# Power.net
KiCad netlist of a schematic drawn in Altium Designer
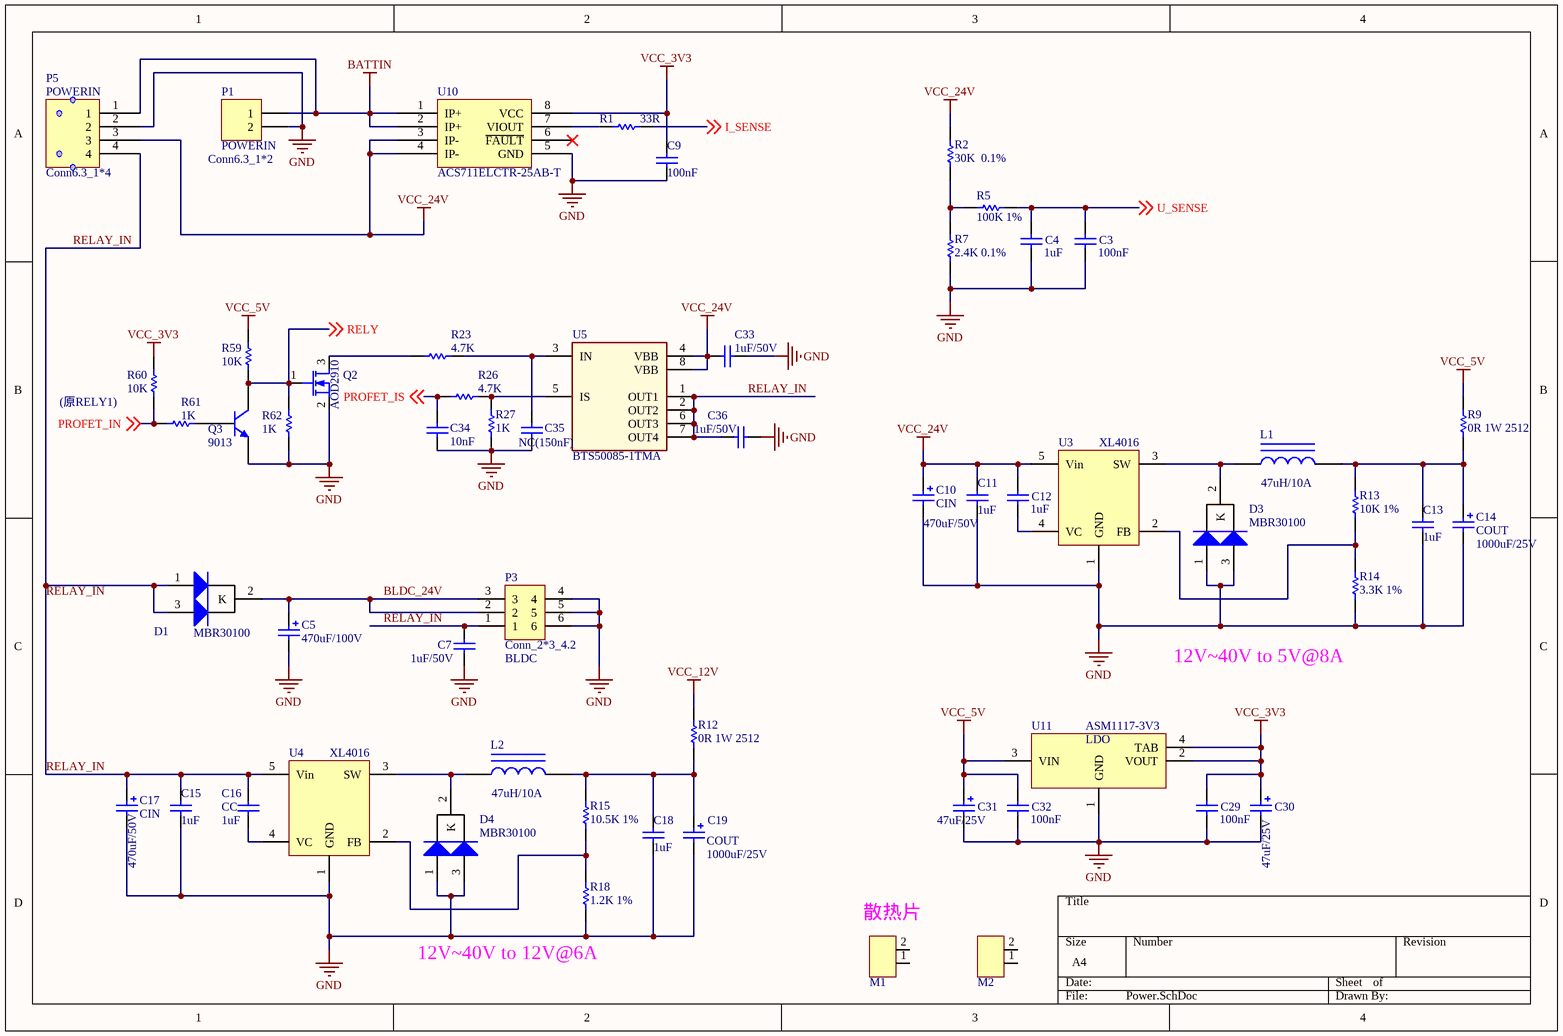
[diagram p0: Power.SchDoc]

(export (version "E")
  (design (tool "Eeschema 10.0.6"))
  (components
    (comp (ref "C3")
      (value "100nF")
      (footprint "C0805")
      (description "Capacitor")
      (fields (field (name "Comment") "Cap") (field (name "PUBLISHER") "Altium Limited"))
      (libsource (lib "boocax_schlib") (part "Cap"))
    )
    (comp (ref "C4")
      (value "1uF")
      (footprint "C0805")
      (description "Capacitor")
      (fields (field (name "Comment") "Cap") (field (name "PUBLISHER") "Altium Limited"))
      (libsource (lib "boocax_schlib") (part "Cap"))
    )
    (comp (ref "C5")
      (value "470uF/100V")
      (footprint "330uF")
      (description "Polarized Capacitor (Radial)")
      (fields (field (name "Comment") "Cap Pol1") (field (name "PUBLISHER") "Altium Limited"))
      (libsource (lib "boocax_schlib") (part "Cap Pol1"))
    )
    (comp (ref "C7")
      (value "1uF/50V")
      (footprint "C0805")
      (description "Capacitor")
      (fields (field (name "Comment") "Cap") (field (name "PUBLISHER") "Altium Limited"))
      (libsource (lib "boocax_schlib") (part "Cap"))
    )
    (comp (ref "C9")
      (value "100nF")
      (footprint "C0805")
      (description "Capacitor")
      (fields (field (name "Comment") "Cap") (field (name "PUBLISHER") "Altium Limited"))
      (libsource (lib "boocax_schlib") (part "Cap"))
    )
    (comp (ref "C10")
      (value "CIN")
      (footprint "CTH-R5-D5")
      (description "Polarized Capacitor (Radial)")
      (fields (field (name "ALTIUM_VALUE") "470uF/50V") (field (name "PUBLISHER") "Altium Limited"))
      (libsource (lib "boocax_schlib") (part "Cap Pol1"))
    )
    (comp (ref "C11")
      (value "1uF")
      (footprint "C0805")
      (description "Capacitor")
      (fields (field (name "Comment") "Cap") (field (name "PUBLISHER") "Altium Limited"))
      (libsource (lib "boocax_schlib") (part "Cap"))
    )
    (comp (ref "C12")
      (value "1uF")
      (footprint "C0805")
      (description "Capacitor")
      (fields (field (name "Comment") "Cap") (field (name "PUBLISHER") "Altium Limited"))
      (libsource (lib "boocax_schlib") (part "Cap"))
    )
    (comp (ref "C13")
      (value "1uF")
      (footprint "C0805")
      (description "Capacitor")
      (fields (field (name "Comment") "Cap") (field (name "PUBLISHER") "Altium Limited"))
      (libsource (lib "boocax_schlib") (part "Cap"))
    )
    (comp (ref "C14")
      (value "COUT")
      (footprint "CTH-R5-D5")
      (description "Polarized Capacitor (Radial)")
      (fields (field (name "ALTIUM_VALUE") "1000uF/25V") (field (name "PUBLISHER") "Altium Limited"))
      (libsource (lib "boocax_schlib") (part "Cap Pol1"))
    )
    (comp (ref "C15")
      (value "1uF")
      (footprint "C0805")
      (description "Capacitor")
      (fields (field (name "Comment") "Cap") (field (name "PUBLISHER") "Altium Limited"))
      (libsource (lib "boocax_schlib") (part "Cap"))
    )
    (comp (ref "C16")
      (value "1uF")
      (footprint "C0805")
      (description "CC")
      (fields (field (name "Comment") "Cap") (field (name "PUBLISHER") "Altium Limited"))
      (libsource (lib "boocax_schlib") (part "Cap"))
    )
    (comp (ref "C17")
      (value "CIN")
      (footprint "CTH-R5-D5")
      (description "Polarized Capacitor (Radial)")
      (fields (field (name "ALTIUM_VALUE") "470uF/50V") (field (name "PUBLISHER") "Altium Limited"))
      (libsource (lib "boocax_schlib") (part "Cap Pol1"))
    )
    (comp (ref "C18")
      (value "1uF")
      (footprint "C0805")
      (description "Capacitor")
      (fields (field (name "Comment") "Cap") (field (name "PUBLISHER") "Altium Limited"))
      (libsource (lib "boocax_schlib") (part "Cap"))
    )
    (comp (ref "C19")
      (value "COUT")
      (footprint "CTH-R5-D5")
      (description "Polarized Capacitor (Radial)")
      (fields (field (name "ALTIUM_VALUE") "1000uF/25V") (field (name "PUBLISHER") "Altium Limited"))
      (libsource (lib "boocax_schlib") (part "Cap Pol1"))
    )
    (comp (ref "C29")
      (value "100nF")
      (footprint "C0805")
      (description "Capacitor")
      (fields (field (name "Comment") "Cap") (field (name "PUBLISHER") "Altium Limited"))
      (libsource (lib "boocax_schlib") (part "Cap"))
    )
    (comp (ref "C30")
      (value "47uF/25V")
      (footprint "CTH-R3-D2.54")
      (description "Polarized Capacitor (Radial)")
      (fields (field (name "Comment") "Cap Pol1") (field (name "PUBLISHER") "Altium Limited"))
      (libsource (lib "boocax_schlib") (part "Cap Pol1"))
    )
    (comp (ref "C31")
      (value "47uF/25V")
      (footprint "CTH-R3-D2.54")
      (description "Polarized Capacitor (Radial)")
      (fields (field (name "Comment") "Cap Pol1") (field (name "PUBLISHER") "Altium Limited"))
      (libsource (lib "boocax_schlib") (part "Cap Pol1"))
    )
    (comp (ref "C32")
      (value "100nF")
      (footprint "C0805")
      (description "Capacitor")
      (fields (field (name "Comment") "Cap") (field (name "PUBLISHER") "Altium Limited"))
      (libsource (lib "boocax_schlib") (part "Cap"))
    )
    (comp (ref "C33")
      (value "1uF/50V")
      (footprint "C0805")
      (description "Capacitor")
      (fields (field (name "Comment") "Cap") (field (name "PUBLISHER") "Altium Limited"))
      (libsource (lib "boocax_schlib") (part "Cap"))
    )
    (comp (ref "C34")
      (value "10nF")
      (footprint "C0805")
      (description "Capacitor")
      (fields (field (name "Comment") "Cap") (field (name "PUBLISHER") "Altium Limited"))
      (libsource (lib "boocax_schlib") (part "Cap"))
    )
    (comp (ref "C35")
      (value "NC(150nF)")
      (footprint "C0805")
      (description "Capacitor")
      (fields (field (name "Comment") "Cap") (field (name "PUBLISHER") "Altium Limited"))
      (libsource (lib "boocax_schlib") (part "Cap"))
    )
    (comp (ref "C36")
      (value "1uF/50V")
      (footprint "C0805")
      (description "Capacitor")
      (fields (field (name "Comment") "Cap") (field (name "PUBLISHER") "Altium Limited"))
      (libsource (lib "boocax_schlib") (part "Cap"))
    )
    (comp (ref "D1")
      (value "MBR30100")
      (footprint "TO-263-3")
      (description "Dual Diode")
      (fields (field (name "PUBLISHER") "Altium Limited"))
      (libsource (lib "boocax_schlib") (part "MBR30100"))
    )
    (comp (ref "D3")
      (value "MBR30100")
      (footprint "BABA03A1:TO-263-3")
      (description "Dual Diode")
      (fields (field (name "PUBLISHER") "Altium Limited"))
      (libsource (lib "boocax_schlib") (part "MBR30100"))
    )
    (comp (ref "D4")
      (value "MBR30100")
      (footprint "BABA03A1:TO-263-3")
      (description "Dual Diode")
      (fields (field (name "PUBLISHER") "Altium Limited"))
      (libsource (lib "boocax_schlib") (part "MBR30100"))
    )
    (comp (ref "L1")
      (value "47uH/10A")
      (footprint "L2210")
      (description "Magnetic-Core Inductor")
      (fields (field (name "Comment") "Inductor Iron") (field (name "PUBLISHER") "Altium Limited"))
      (libsource (lib "boocax_schlib") (part "Inductor Iron"))
    )
    (comp (ref "L2")
      (value "47uH/10A")
      (footprint "L2210")
      (description "Magnetic-Core Inductor")
      (fields (field (name "Comment") "Inductor Iron") (field (name "PUBLISHER") "Altium Limited"))
      (libsource (lib "boocax_schlib") (part "Inductor Iron"))
    )
    (comp (ref "M1")
      (value "SRP")
      (footprint "BABA03A1:SRP-2-15*10")
      (libsource (lib "boocax_schlib") (part "SRP-1"))
    )
    (comp (ref "M2")
      (value "SRP")
      (footprint "BABA03A1:SRP-2-15*10")
      (libsource (lib "boocax_schlib") (part "SRP-1"))
    )
    (comp (ref "P1")
      (value "POWERIN")
      (footprint "DIP2*6.3")
      (description "Conn6.3_1*2")
      (libsource (lib "Miscellaneous Connectors") (part "Header 2"))
    )
    (comp (ref "P3")
      (value "Conn_2*3_4.2")
      (footprint "PIN2X3_4.2")
      (fields (field (name "CONN4.2") "BLDC"))
      (libsource (lib "boocax_schlib") (part "Conn_2*3_4.2"))
    )
    (comp (ref "P5")
      (value "POWERIN")
      (footprint "boocax_schlib:PORT-SIP4-6.3-LOCK")
      (fields (field (name "ALTIUM_UNNAMED_1") "Conn6.3_1*4"))
      (libsource (lib "boocax_schlib") (part "CONN_4PIN"))
    )
    (comp (ref "Q2")
      (value "AOD2910")
      (footprint "boocax_schlib:TO252-D")
      (description "N-Channel MOSFET")
      (fields (field (name "PUBLISHER") "Altium Limited"))
      (libsource (lib "boocax_schlib") (part "MOSFET-N"))
    )
    (comp (ref "Q3")
      (value "9013")
      (footprint "boocax_schlib:BCY-W3/E4")
      (description "NPN General Purpose Amplifier")
      (fields (field (name "PUBLISHER") "Altium Limited"))
      (libsource (lib "Miscellaneous Devices") (part "2N3904"))
    )
    (comp (ref "R1")
      (value "33R")
      (footprint "R0805")
      (description "Resistor")
      (fields (field (name "Comment") "Res1") (field (name "PUBLISHER") "Altium Limited"))
      (libsource (lib "boocax_schlib") (part "Res1"))
    )
    (comp (ref "R2")
      (value "30K  0.1%")
      (footprint "R0805")
      (description "Resistor")
      (fields (field (name "Comment") "Res1") (field (name "PUBLISHER") "Altium Limited"))
      (libsource (lib "boocax_schlib") (part "Res1"))
    )
    (comp (ref "R5")
      (value "100K 1%")
      (footprint "R0805")
      (description "Resistor")
      (fields (field (name "Comment") "Res1") (field (name "PUBLISHER") "Altium Limited"))
      (libsource (lib "boocax_schlib") (part "Res1"))
    )
    (comp (ref "R7")
      (value "2.4K 0.1%")
      (footprint "R0805")
      (description "Resistor")
      (fields (field (name "Comment") "Res1") (field (name "PUBLISHER") "Altium Limited"))
      (libsource (lib "boocax_schlib") (part "Res1"))
    )
    (comp (ref "R9")
      (value "0R 1W 2512")
      (footprint "2512")
      (description "Resistor")
      (fields (field (name "Comment") "Res1") (field (name "PUBLISHER") "Altium Limited"))
      (libsource (lib "boocax_schlib") (part "Res1"))
    )
    (comp (ref "R12")
      (value "0R 1W 2512")
      (footprint "2512")
      (description "Resistor")
      (fields (field (name "Comment") "Res1") (field (name "PUBLISHER") "Altium Limited"))
      (libsource (lib "boocax_schlib") (part "Res1"))
    )
    (comp (ref "R13")
      (value "10K 1%")
      (footprint "R0805")
      (description "Resistor")
      (fields (field (name "Comment") "Res1") (field (name "PUBLISHER") "Altium Limited"))
      (libsource (lib "boocax_schlib") (part "Res1"))
    )
    (comp (ref "R14")
      (value "3.3K 1%")
      (footprint "R0805")
      (description "Resistor")
      (fields (field (name "Comment") "Res1") (field (name "PUBLISHER") "Altium Limited"))
      (libsource (lib "boocax_schlib") (part "Res1"))
    )
    (comp (ref "R15")
      (value "10.5K 1%")
      (footprint "R0805")
      (description "Resistor")
      (fields (field (name "Comment") "Res1") (field (name "PUBLISHER") "Altium Limited"))
      (libsource (lib "boocax_schlib") (part "Res1"))
    )
    (comp (ref "R18")
      (value "1.2K 1%")
      (footprint "R0805")
      (description "Resistor")
      (fields (field (name "Comment") "Res1") (field (name "PUBLISHER") "Altium Limited"))
      (libsource (lib "boocax_schlib") (part "Res1"))
    )
    (comp (ref "R23")
      (value "4.7K")
      (footprint "R0805")
      (description "Resistor")
      (fields (field (name "Comment") "Res1") (field (name "PUBLISHER") "Altium Limited"))
      (libsource (lib "boocax_schlib") (part "Res1"))
    )
    (comp (ref "R26")
      (value "4.7K")
      (footprint "R0805")
      (description "Resistor")
      (fields (field (name "Comment") "Res1") (field (name "PUBLISHER") "Altium Limited"))
      (libsource (lib "boocax_schlib") (part "Res1"))
    )
    (comp (ref "R27")
      (value "1K")
      (footprint "R0805")
      (description "Resistor")
      (fields (field (name "Comment") "Res1") (field (name "PUBLISHER") "Altium Limited"))
      (libsource (lib "boocax_schlib") (part "Res1"))
    )
    (comp (ref "R59")
      (value "10K")
      (footprint "R0805")
      (description "Resistor")
      (fields (field (name "Comment") "Res1") (field (name "PUBLISHER") "Altium Limited"))
      (libsource (lib "boocax_schlib") (part "Res1"))
    )
    (comp (ref "R60")
      (value "10K")
      (footprint "R0805")
      (description "Resistor")
      (fields (field (name "Comment") "Res1") (field (name "PUBLISHER") "Altium Limited"))
      (libsource (lib "boocax_schlib") (part "Res1"))
    )
    (comp (ref "R61")
      (value "1K")
      (footprint "R0805")
      (description "Resistor")
      (fields (field (name "Comment") "Res1") (field (name "PUBLISHER") "Altium Limited"))
      (libsource (lib "boocax_schlib") (part "Res1"))
    )
    (comp (ref "R62")
      (value "1K")
      (footprint "R0805")
      (description "Resistor")
      (fields (field (name "Comment") "Res1") (field (name "PUBLISHER") "Altium Limited"))
      (libsource (lib "boocax_schlib") (part "Res1"))
    )
    (comp (ref "U3")
      (value "XL4016")
      (footprint "TO220-5")
      (description "BUCK DCDC")
      (fields (field (name "PUBLISHER") "Altium Limited"))
      (libsource (lib "boocax_schlib") (part "XL4016"))
    )
    (comp (ref "U4")
      (value "XL4016")
      (footprint "TO220-5")
      (description "BUCK DCDC")
      (fields (field (name "PUBLISHER") "Altium Limited"))
      (libsource (lib "boocax_schlib") (part "XL4016"))
    )
    (comp (ref "U5")
      (value "BTS50085-1TMA")
      (footprint "boocax_schlib:TO127P1385X450-8N-V")
      (description "Smart Highside High Current Power Switch, VBB 70V")
      (fields (field (name "MANUFACTURER") "Infineon Technologies"))
      (libsource (lib "boocax_schlib") (part "BTS50085-1TMA"))
    )
    (comp (ref "U10")
      (value "ACS711ELCTR-25AB-T")
      (footprint "ACS712-SOIC8")
      (libsource (lib "BABA03A-V1") (part "ACS711"))
    )
    (comp (ref "U11")
      (value "ASM1117-3V3")
      (footprint "boocax_schlib:ASM1117-3V3")
      (libsource (lib "boocax_schlib") (part "LDO"))
    )
  )
  (nets
    (net (code "1") (name "/BLDC_24V") (class "Default")
      (node (ref "C5") (pin "1") (pinfunction "1_1") (pintype "passive"))
      (node (ref "D1") (pin "2") (pinfunction "K_2") (pintype "passive"))
      (node (ref "P3") (pin "2") (pinfunction "2_2") (pintype "passive"))
      (node (ref "P3") (pin "3") (pinfunction "3_3") (pintype "passive"))
    )
    (net (code "2") (name "/RELAY_IN") (class "Default")
      (node (ref "C15") (pin "2") (pinfunction "2_2") (pintype "passive"))
      (node (ref "C16") (pin "2") (pinfunction "2_2") (pintype "passive"))
      (node (ref "C17") (pin "1") (pinfunction "1_1") (pintype "passive"))
      (node (ref "C36") (pin "2") (pinfunction "2_2") (pintype "passive"))
      (node (ref "C7") (pin "1") (pinfunction "1_1") (pintype "passive"))
      (node (ref "D1") (pin "1") (pinfunction "A_1") (pintype "passive"))
      (node (ref "D1") (pin "3") (pinfunction "A_3") (pintype "passive"))
      (node (ref "P3") (pin "1") (pinfunction "1_1") (pintype "passive"))
      (node (ref "P5") (pin "4") (pinfunction "4_4") (pintype "passive"))
      (node (ref "U4") (pin "5") (pinfunction "Vin_5") (pintype "passive"))
      (node (ref "U5") (pin "1") (pinfunction "OUT1_1") (pintype "passive"))
      (node (ref "U5") (pin "2") (pinfunction "OUT2_2") (pintype "passive"))
      (node (ref "U5") (pin "6") (pinfunction "OUT3_6") (pintype "passive"))
      (node (ref "U5") (pin "7") (pinfunction "OUT4_7") (pintype "passive"))
    )
    (net (code "3") (name "BATTIN") (class "Default")
      (node (ref "P1") (pin "1") (pinfunction "1_1") (pintype "passive"))
      (node (ref "P5") (pin "1") (pinfunction "1_1") (pintype "passive"))
      (node (ref "U10") (pin "1") (pinfunction "IP+_1") (pintype "passive"))
      (node (ref "U10") (pin "2") (pinfunction "IP+_2") (pintype "passive"))
    )
    (net (code "4") (name "GND") (class "Default")
      (node (ref "C10") (pin "2") (pinfunction "2_2") (pintype "passive"))
      (node (ref "C11") (pin "1") (pinfunction "1_1") (pintype "passive"))
      (node (ref "C13") (pin "1") (pinfunction "1_1") (pintype "passive"))
      (node (ref "C14") (pin "2") (pinfunction "2_2") (pintype "passive"))
      (node (ref "C15") (pin "1") (pinfunction "1_1") (pintype "passive"))
      (node (ref "C17") (pin "2") (pinfunction "2_2") (pintype "passive"))
      (node (ref "C18") (pin "1") (pinfunction "1_1") (pintype "passive"))
      (node (ref "C19") (pin "2") (pinfunction "2_2") (pintype "passive"))
      (node (ref "C29") (pin "1") (pinfunction "1_1") (pintype "passive"))
      (node (ref "C3") (pin "1") (pinfunction "1_1") (pintype "passive"))
      (node (ref "C30") (pin "2") (pinfunction "2_2") (pintype "passive"))
      (node (ref "C31") (pin "2") (pinfunction "2_2") (pintype "passive"))
      (node (ref "C32") (pin "1") (pinfunction "1_1") (pintype "passive"))
      (node (ref "C33") (pin "1") (pinfunction "1_1") (pintype "passive"))
      (node (ref "C34") (pin "2") (pinfunction "2_2") (pintype "passive"))
      (node (ref "C35") (pin "2") (pinfunction "2_2") (pintype "passive"))
      (node (ref "C36") (pin "1") (pinfunction "1_1") (pintype "passive"))
      (node (ref "C4") (pin "1") (pinfunction "1_1") (pintype "passive"))
      (node (ref "C5") (pin "2") (pinfunction "2_2") (pintype "passive"))
      (node (ref "C7") (pin "2") (pinfunction "2_2") (pintype "passive"))
      (node (ref "C9") (pin "1") (pinfunction "1_1") (pintype "passive"))
      (node (ref "D3") (pin "1") (pinfunction "A_1") (pintype "passive"))
      (node (ref "D3") (pin "3") (pinfunction "A_3") (pintype "passive"))
      (node (ref "D4") (pin "1") (pinfunction "A_1") (pintype "passive"))
      (node (ref "D4") (pin "3") (pinfunction "A_3") (pintype "passive"))
      (node (ref "P1") (pin "2") (pinfunction "2_2") (pintype "passive"))
      (node (ref "P3") (pin "4") (pinfunction "4_4") (pintype "passive"))
      (node (ref "P3") (pin "5") (pinfunction "5_5") (pintype "passive"))
      (node (ref "P3") (pin "6") (pinfunction "6_6") (pintype "passive"))
      (node (ref "P5") (pin "2") (pinfunction "2_2") (pintype "passive"))
      (node (ref "Q2") (pin "2") (pinfunction "S_2") (pintype "passive"))
      (node (ref "Q3") (pin "1") (pinfunction "E_1") (pintype "passive"))
      (node (ref "R14") (pin "2") (pinfunction "2_2") (pintype "passive"))
      (node (ref "R18") (pin "2") (pinfunction "2_2") (pintype "passive"))
      (node (ref "R27") (pin "1") (pinfunction "1_1") (pintype "passive"))
      (node (ref "R62") (pin "2") (pinfunction "2_2") (pintype "passive"))
      (node (ref "R7") (pin "2") (pinfunction "2_2") (pintype "passive"))
      (node (ref "U10") (pin "5") (pinfunction "GND_5") (pintype "passive"))
      (node (ref "U11") (pin "1") (pinfunction "GND_1") (pintype "passive"))
      (node (ref "U3") (pin "1") (pinfunction "GND_1") (pintype "passive"))
      (node (ref "U4") (pin "1") (pinfunction "GND_1") (pintype "passive"))
    )
    (net (code "5") (name "I_SENSE") (class "Default")
      (node (ref "R1") (pin "1") (pinfunction "1_1") (pintype "passive"))
    )
    (net (code "6") (name "Net-(C13-Pad2)") (class "Default")
      (node (ref "C13") (pin "2") (pinfunction "2_2") (pintype "passive"))
      (node (ref "C14") (pin "1") (pinfunction "1_1") (pintype "passive"))
      (node (ref "L1") (pin "2") (pinfunction "2_2") (pintype "passive"))
      (node (ref "R13") (pin "1") (pinfunction "1_1") (pintype "passive"))
      (node (ref "R9") (pin "2") (pinfunction "2_2") (pintype "passive"))
    )
    (net (code "7") (name "Net-(C18-Pad2)") (class "Default")
      (node (ref "C18") (pin "2") (pinfunction "2_2") (pintype "passive"))
      (node (ref "C19") (pin "1") (pinfunction "1_1") (pintype "passive"))
      (node (ref "L2") (pin "2") (pinfunction "2_2") (pintype "passive"))
      (node (ref "R12") (pin "2") (pinfunction "2_2") (pintype "passive"))
      (node (ref "R15") (pin "1") (pinfunction "1_1") (pintype "passive"))
    )
    (net (code "8") (name "Net-(D3-K)") (class "Default")
      (node (ref "D3") (pin "2") (pinfunction "K_2") (pintype "passive"))
      (node (ref "L1") (pin "1") (pinfunction "1_1") (pintype "passive"))
      (node (ref "U3") (pin "3") (pinfunction "SW_3") (pintype "passive"))
    )
    (net (code "9") (name "Net-(D4-K)") (class "Default")
      (node (ref "D4") (pin "2") (pinfunction "K_2") (pintype "passive"))
      (node (ref "L2") (pin "1") (pinfunction "1_1") (pintype "passive"))
      (node (ref "U4") (pin "3") (pinfunction "SW_3") (pintype "passive"))
    )
    (net (code "10") (name "Net-(Q2-D)") (class "Default")
      (node (ref "Q2") (pin "3") (pinfunction "D_3") (pintype "passive"))
      (node (ref "R23") (pin "1") (pinfunction "1_1") (pintype "passive"))
    )
    (net (code "11") (name "Net-(Q3-B)") (class "Default")
      (node (ref "Q3") (pin "2") (pinfunction "B_2") (pintype "passive"))
      (node (ref "R61") (pin "1") (pinfunction "1_1") (pintype "passive"))
    )
    (net (code "12") (name "Net-(R2-Pad2)") (class "Default")
      (node (ref "R2") (pin "2") (pinfunction "2_2") (pintype "passive"))
      (node (ref "R5") (pin "1") (pinfunction "1_1") (pintype "passive"))
      (node (ref "R7") (pin "1") (pinfunction "1_1") (pintype "passive"))
    )
    (net (code "13") (name "Net-(U3-FB)") (class "Default")
      (node (ref "R13") (pin "2") (pinfunction "2_2") (pintype "passive"))
      (node (ref "R14") (pin "1") (pinfunction "1_1") (pintype "passive"))
      (node (ref "U3") (pin "2") (pinfunction "FB_2") (pintype "passive"))
    )
    (net (code "14") (name "Net-(U3-VC)") (class "Default")
      (node (ref "C12") (pin "1") (pinfunction "1_1") (pintype "passive"))
      (node (ref "U3") (pin "4") (pinfunction "VC_4") (pintype "passive"))
    )
    (net (code "15") (name "Net-(U4-FB)") (class "Default")
      (node (ref "R15") (pin "2") (pinfunction "2_2") (pintype "passive"))
      (node (ref "R18") (pin "1") (pinfunction "1_1") (pintype "passive"))
      (node (ref "U4") (pin "2") (pinfunction "FB_2") (pintype "passive"))
    )
    (net (code "16") (name "Net-(U4-VC)") (class "Default")
      (node (ref "C16") (pin "1") (pinfunction "1_1") (pintype "passive"))
      (node (ref "U4") (pin "4") (pinfunction "VC_4") (pintype "passive"))
    )
    (net (code "17") (name "Net-(U5-IN)") (class "Default")
      (node (ref "C35") (pin "1") (pinfunction "1_1") (pintype "passive"))
      (node (ref "R23") (pin "2") (pinfunction "2_2") (pintype "passive"))
      (node (ref "U5") (pin "3") (pinfunction "IN_3") (pintype "passive"))
    )
    (net (code "18") (name "Net-(U5-IS)") (class "Default")
      (node (ref "R26") (pin "2") (pinfunction "2_2") (pintype "passive"))
      (node (ref "R27") (pin "2") (pinfunction "2_2") (pintype "passive"))
      (node (ref "U5") (pin "5") (pinfunction "IS_5") (pintype "passive"))
    )
    (net (code "19") (name "Net-(U10-VIOUT)") (class "Default")
      (node (ref "R1") (pin "2") (pinfunction "2_2") (pintype "passive"))
      (node (ref "U10") (pin "7") (pinfunction "VIOUT_7") (pintype "passive"))
    )
    (net (code "20") (name "PROFET_IN") (class "Default")
      (node (ref "R60") (pin "2") (pinfunction "2_2") (pintype "passive"))
      (node (ref "R61") (pin "2") (pinfunction "2_2") (pintype "passive"))
    )
    (net (code "21") (name "PROFET_IS") (class "Default")
      (node (ref "C34") (pin "1") (pinfunction "1_1") (pintype "passive"))
      (node (ref "R26") (pin "1") (pinfunction "1_1") (pintype "passive"))
    )
    (net (code "22") (name "RELY") (class "Default")
      (node (ref "Q2") (pin "1") (pinfunction "G_1") (pintype "passive"))
      (node (ref "Q3") (pin "3") (pinfunction "C_3") (pintype "passive"))
      (node (ref "R59") (pin "2") (pinfunction "2_2") (pintype "passive"))
      (node (ref "R62") (pin "1") (pinfunction "1_1") (pintype "passive"))
    )
    (net (code "23") (name "U_SENSE") (class "Default")
      (node (ref "C3") (pin "2") (pinfunction "2_2") (pintype "passive"))
      (node (ref "C4") (pin "2") (pinfunction "2_2") (pintype "passive"))
      (node (ref "R5") (pin "2") (pinfunction "2_2") (pintype "passive"))
    )
    (net (code "24") (name "VCC_3V3") (class "Default")
      (node (ref "C29") (pin "2") (pinfunction "2_2") (pintype "passive"))
      (node (ref "C30") (pin "1") (pinfunction "1_1") (pintype "passive"))
      (node (ref "C9") (pin "2") (pinfunction "2_2") (pintype "passive"))
      (node (ref "R60") (pin "1") (pinfunction "1_1") (pintype "passive"))
      (node (ref "U10") (pin "8") (pinfunction "VCC_8") (pintype "passive"))
      (node (ref "U11") (pin "2") (pinfunction "VOUT_2") (pintype "passive"))
      (node (ref "U11") (pin "4") (pinfunction "TAB_4") (pintype "passive"))
    )
    (net (code "25") (name "VCC_5V") (class "Default")
      (node (ref "C31") (pin "1") (pinfunction "1_1") (pintype "passive"))
      (node (ref "C32") (pin "2") (pinfunction "2_2") (pintype "passive"))
      (node (ref "R59") (pin "1") (pinfunction "1_1") (pintype "passive"))
      (node (ref "R9") (pin "1") (pinfunction "1_1") (pintype "passive"))
      (node (ref "U11") (pin "3") (pinfunction "VIN_3") (pintype "passive"))
    )
    (net (code "26") (name "VCC_12V") (class "Default")
      (node (ref "R12") (pin "1") (pinfunction "1_1") (pintype "passive"))
    )
    (net (code "27") (name "VCC_24V") (class "Default")
      (node (ref "C10") (pin "1") (pinfunction "1_1") (pintype "passive"))
      (node (ref "C11") (pin "2") (pinfunction "2_2") (pintype "passive"))
      (node (ref "C12") (pin "2") (pinfunction "2_2") (pintype "passive"))
      (node (ref "C33") (pin "2") (pinfunction "2_2") (pintype "passive"))
      (node (ref "P5") (pin "3") (pinfunction "3_3") (pintype "passive"))
      (node (ref "R2") (pin "1") (pinfunction "1_1") (pintype "passive"))
      (node (ref "U10") (pin "3") (pinfunction "IP-_3") (pintype "passive"))
      (node (ref "U10") (pin "4") (pinfunction "IP-_4") (pintype "passive"))
      (node (ref "U3") (pin "5") (pinfunction "Vin_5") (pintype "passive"))
      (node (ref "U5") (pin "4") (pinfunction "VBB_4") (pintype "power_in"))
      (node (ref "U5") (pin "8") (pinfunction "VBB_8") (pintype "power_in"))
    )
    (net (code "28") (name "unconnected-(M1-Pad1)") (class "Default")
      (node (ref "M1") (pin "1") (pinfunction "1_1") (pintype "passive"))
    )
    (net (code "29") (name "unconnected-(M1-Pad2)") (class "Default")
      (node (ref "M1") (pin "2") (pinfunction "2_2") (pintype "passive"))
    )
    (net (code "30") (name "unconnected-(M2-Pad1)") (class "Default")
      (node (ref "M2") (pin "1") (pinfunction "1_1") (pintype "passive"))
    )
    (net (code "31") (name "unconnected-(M2-Pad2)") (class "Default")
      (node (ref "M2") (pin "2") (pinfunction "2_2") (pintype "passive"))
    )
    (net (code "32") (name "unconnected-(U10-~{FAULT}-Pad6)") (class "Default")
      (node (ref "U10") (pin "6") (pinfunction "~{FAULT}_6") (pintype "passive+no_connect"))
    )
  )
)
